# MSP432E401YTPDT_MCU.net
KiCad netlist of a schematic drawn in Altium Designer
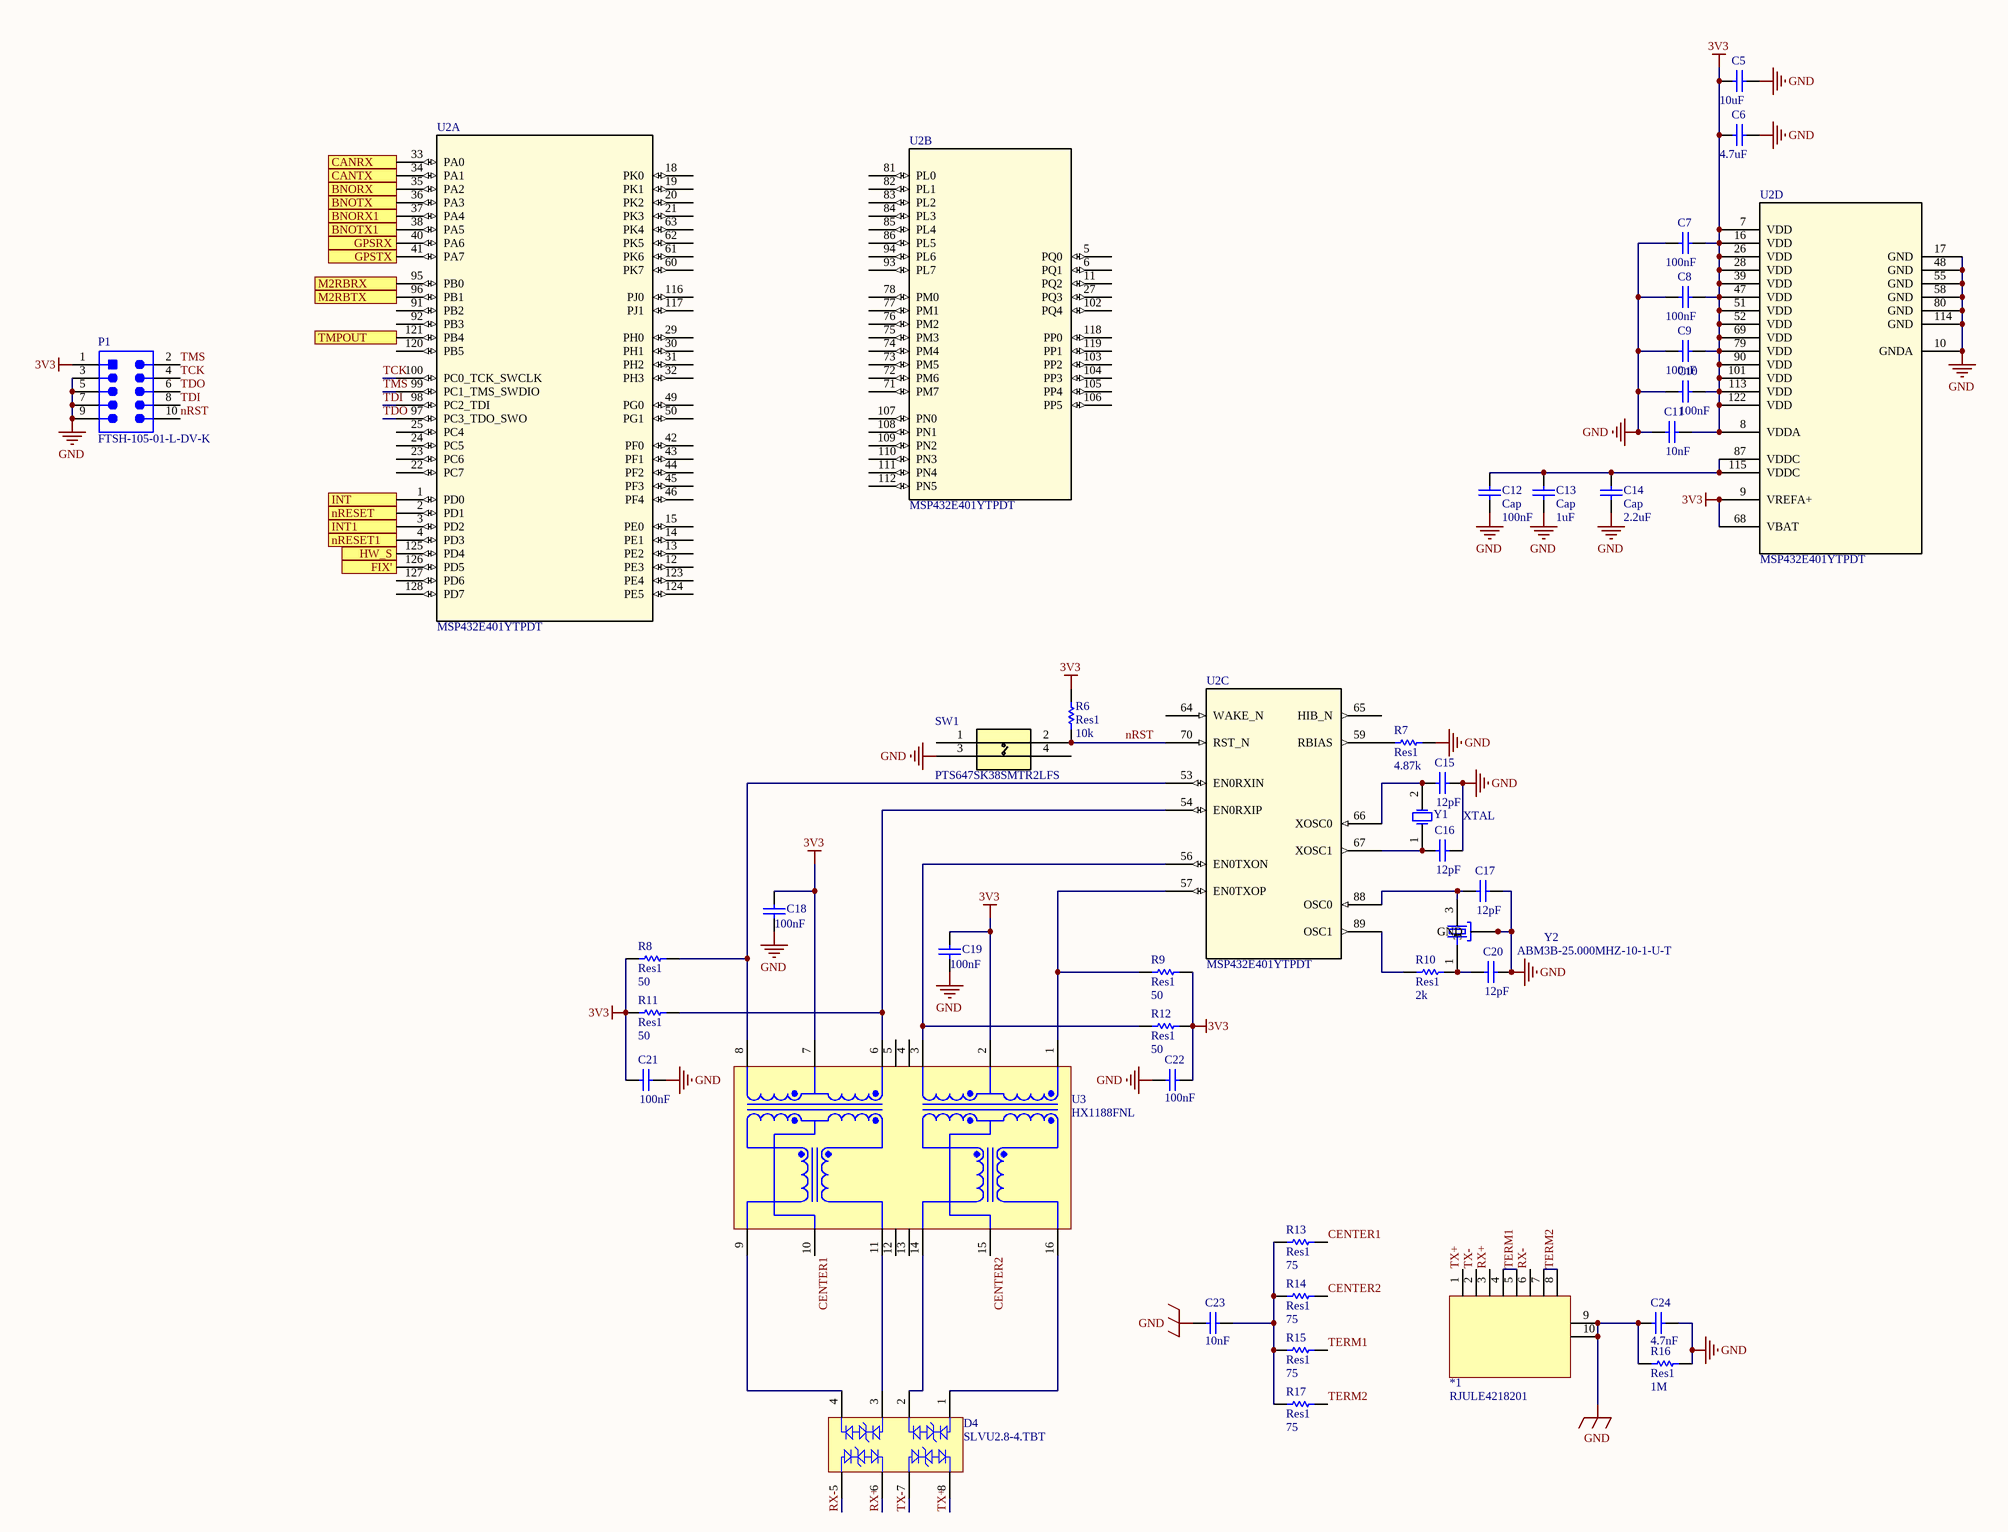
[diagram p0: MSP432E401YTPDT MCU.SchDoc]

(export (version "E")
  (design (tool "Eeschema 10.0.6"))
  (components
    (comp (ref "*1")
      (value "RJULE4218201")
      (footprint "RJULE4218201")
      (libsource (lib "RJULE4218201") (part "RJULE4218201"))
    )
    (comp (ref "C5")
      (value "10uF")
      (footprint "6-0805_M")
      (description "Capacitor")
      (fields (field (name "Comment") "Cap") (field (name "PUBLISHER") "Altium Limited"))
      (libsource (lib "Miscellaneous Devices") (part "Cap"))
    )
    (comp (ref "C6")
      (value "4.7uF")
      (footprint "6-0805_M")
      (description "Capacitor")
      (fields (field (name "Comment") "Cap") (field (name "PUBLISHER") "Altium Limited"))
      (libsource (lib "Miscellaneous Devices") (part "Cap"))
    )
    (comp (ref "C7")
      (value "100nF")
      (footprint "0402-A")
      (description "Capacitor")
      (fields (field (name "Comment") "Cap") (field (name "PUBLISHER") "Altium Limited"))
      (libsource (lib "Miscellaneous Devices") (part "Cap"))
    )
    (comp (ref "C8")
      (value "100nF")
      (footprint "0402-A")
      (description "Capacitor")
      (fields (field (name "Comment") "Cap") (field (name "PUBLISHER") "Altium Limited"))
      (libsource (lib "Miscellaneous Devices") (part "Cap"))
    )
    (comp (ref "C9")
      (value "100nF")
      (footprint "0402-A")
      (description "Capacitor")
      (fields (field (name "Comment") "Cap") (field (name "PUBLISHER") "Altium Limited"))
      (libsource (lib "Miscellaneous Devices") (part "Cap"))
    )
    (comp (ref "C10")
      (value "100nF")
      (footprint "0402-A")
      (description "Capacitor")
      (fields (field (name "Comment") "Cap") (field (name "PUBLISHER") "Altium Limited"))
      (libsource (lib "Miscellaneous Devices") (part "Cap"))
    )
    (comp (ref "C11")
      (value "10nF")
      (footprint "0402-A")
      (description "Capacitor")
      (fields (field (name "Comment") "Cap") (field (name "PUBLISHER") "Altium Limited"))
      (libsource (lib "Miscellaneous Devices") (part "Cap"))
    )
    (comp (ref "C12")
      (value "Cap")
      (footprint "0402-A")
      (description "Capacitor")
      (fields (field (name "ALTIUM_VALUE") "100nF") (field (name "PUBLISHER") "Altium Limited"))
      (libsource (lib "Miscellaneous Devices") (part "Cap"))
    )
    (comp (ref "C13")
      (value "Cap")
      (footprint "1608[0603]")
      (description "Capacitor")
      (fields (field (name "ALTIUM_VALUE") "1uF") (field (name "PUBLISHER") "Altium Limited"))
      (libsource (lib "Miscellaneous Devices") (part "Cap"))
    )
    (comp (ref "C14")
      (value "Cap")
      (footprint "1608[0603]")
      (description "Capacitor")
      (fields (field (name "ALTIUM_VALUE") "2.2uF") (field (name "PUBLISHER") "Altium Limited"))
      (libsource (lib "Miscellaneous Devices") (part "Cap"))
    )
    (comp (ref "C15")
      (value "12pF")
      (footprint "0402-A")
      (description "Capacitor")
      (fields (field (name "Comment") "Cap") (field (name "PUBLISHER") "Altium Limited"))
      (libsource (lib "Miscellaneous Devices") (part "Cap"))
    )
    (comp (ref "C16")
      (value "12pF")
      (footprint "0402-A")
      (description "Capacitor")
      (fields (field (name "Comment") "Cap") (field (name "PUBLISHER") "Altium Limited"))
      (libsource (lib "Miscellaneous Devices") (part "Cap"))
    )
    (comp (ref "C17")
      (value "12pF")
      (footprint "0402-A")
      (description "Capacitor")
      (fields (field (name "Comment") "Cap") (field (name "PUBLISHER") "Altium Limited"))
      (libsource (lib "Miscellaneous Devices") (part "Cap"))
    )
    (comp (ref "C18")
      (value "100nF")
      (footprint "0402-A")
      (description "Capacitor")
      (fields (field (name "Comment") "Cap") (field (name "PUBLISHER") "Altium Limited"))
      (libsource (lib "Miscellaneous Devices") (part "Cap"))
    )
    (comp (ref "C19")
      (value "100nF")
      (footprint "0402-A")
      (description "Capacitor")
      (fields (field (name "Comment") "Cap") (field (name "PUBLISHER") "Altium Limited"))
      (libsource (lib "Miscellaneous Devices") (part "Cap"))
    )
    (comp (ref "C20")
      (value "12pF")
      (footprint "0402-A")
      (description "Capacitor")
      (fields (field (name "Comment") "Cap") (field (name "PUBLISHER") "Altium Limited"))
      (libsource (lib "Miscellaneous Devices") (part "Cap"))
    )
    (comp (ref "C21")
      (value "100nF")
      (footprint "0402-A")
      (description "Capacitor")
      (fields (field (name "Comment") "Cap") (field (name "PUBLISHER") "Altium Limited"))
      (libsource (lib "Miscellaneous Devices") (part "Cap"))
    )
    (comp (ref "C22")
      (value "100nF")
      (footprint "0402-A")
      (description "Capacitor")
      (fields (field (name "Comment") "Cap") (field (name "PUBLISHER") "Altium Limited"))
      (libsource (lib "Miscellaneous Devices") (part "Cap"))
    )
    (comp (ref "C23")
      (value "10nF")
      (footprint "0402-A")
      (description "Capacitor")
      (fields (field (name "Comment") "Cap") (field (name "PUBLISHER") "Altium Limited"))
      (libsource (lib "Miscellaneous Devices") (part "Cap"))
    )
    (comp (ref "C24")
      (value "4.7nF")
      (footprint "C1206")
      (description "Capacitor")
      (fields (field (name "Comment") "Cap") (field (name "PUBLISHER") "Altium Limited"))
      (libsource (lib "Miscellaneous Devices") (part "Cap"))
    )
    (comp (ref "D4")
      (value "SLVU2.8-4.TBT")
      (footprint "SEMT-SO-8_V")
      (fields (field (name "MANUFACTURER") "Semtech"))
      (libsource (lib "Altium Content Vault") (part "SEMT-SLVU2.8-4-SO-8"))
    )
    (comp (ref "P1")
      (value "FTSH-105-01-L-DV-K")
      (footprint "SMTC-FTSH-105-01-L-DV-K_V")
      (description "Male Header, Pitch 1.27 mm, 2 x 5 Position, Height 6.25 mm")
      (fields (field (name "MANUFACTURER") "Samtec"))
      (libsource (lib "Altium Content Vault") (part "CN-2P-M-R10"))
    )
    (comp (ref "R6")
      (value "Res1")
      (footprint "0402-A")
      (description "Resistor")
      (fields (field (name "ALTIUM_VALUE") "10k") (field (name "PUBLISHER") "Altium Limited"))
      (libsource (lib "Miscellaneous Devices") (part "Res1"))
    )
    (comp (ref "R7")
      (value "Res1")
      (footprint "0402-A")
      (description "Resistor")
      (fields (field (name "ALTIUM_VALUE") "4.87k") (field (name "PUBLISHER") "Altium Limited"))
      (libsource (lib "Miscellaneous Devices") (part "Res1"))
    )
    (comp (ref "R8")
      (value "Res1")
      (footprint "0402-A")
      (description "Resistor")
      (fields (field (name "ALTIUM_VALUE") "50") (field (name "PUBLISHER") "Altium Limited"))
      (libsource (lib "Miscellaneous Devices") (part "Res1"))
    )
    (comp (ref "R9")
      (value "Res1")
      (footprint "0402-A")
      (description "Resistor")
      (fields (field (name "ALTIUM_VALUE") "50") (field (name "PUBLISHER") "Altium Limited"))
      (libsource (lib "Miscellaneous Devices") (part "Res1"))
    )
    (comp (ref "R10")
      (value "Res1")
      (footprint "0402-A")
      (description "Resistor")
      (fields (field (name "ALTIUM_VALUE") "2k") (field (name "PUBLISHER") "Altium Limited"))
      (libsource (lib "Miscellaneous Devices") (part "Res1"))
    )
    (comp (ref "R11")
      (value "Res1")
      (footprint "0402-A")
      (description "Resistor")
      (fields (field (name "ALTIUM_VALUE") "50") (field (name "PUBLISHER") "Altium Limited"))
      (libsource (lib "Miscellaneous Devices") (part "Res1"))
    )
    (comp (ref "R12")
      (value "Res1")
      (footprint "0402-A")
      (description "Resistor")
      (fields (field (name "ALTIUM_VALUE") "50") (field (name "PUBLISHER") "Altium Limited"))
      (libsource (lib "Miscellaneous Devices") (part "Res1"))
    )
    (comp (ref "R13")
      (value "Res1")
      (footprint "0402-A")
      (description "Resistor")
      (fields (field (name "ALTIUM_VALUE") "75") (field (name "PUBLISHER") "Altium Limited"))
      (libsource (lib "Miscellaneous Devices") (part "Res1"))
    )
    (comp (ref "R14")
      (value "Res1")
      (footprint "0402-A")
      (description "Resistor")
      (fields (field (name "ALTIUM_VALUE") "75") (field (name "PUBLISHER") "Altium Limited"))
      (libsource (lib "Miscellaneous Devices") (part "Res1"))
    )
    (comp (ref "R15")
      (value "Res1")
      (footprint "0402-A")
      (description "Resistor")
      (fields (field (name "ALTIUM_VALUE") "75") (field (name "PUBLISHER") "Altium Limited"))
      (libsource (lib "Miscellaneous Devices") (part "Res1"))
    )
    (comp (ref "R16")
      (value "Res1")
      (footprint "C1206")
      (description "Resistor")
      (fields (field (name "ALTIUM_VALUE") "1M") (field (name "PUBLISHER") "Altium Limited"))
      (libsource (lib "Miscellaneous Devices") (part "Res1"))
    )
    (comp (ref "R17")
      (value "Res1")
      (footprint "0402-A")
      (description "Resistor")
      (fields (field (name "ALTIUM_VALUE") "75") (field (name "PUBLISHER") "Altium Limited"))
      (libsource (lib "Miscellaneous Devices") (part "Res1"))
    )
    (comp (ref "SW1")
      (value "PTS647SK38SMTR2LFS")
      (footprint "PTS647SK38SMTR2LFS_CNK")
      (description "No Description Available")
      (fields (field (name "COPYRIGHT") "Copyright (C) 2018 Accelerated Designs. All rights reserved"))
      (libsource (lib "PTS 647 SK38 SMTR2 LFS") (part "PTS647SK38SMTR2LFS"))
    )
    (comp (ref "U2")
      (value "MSP432E401YTPDT")
      (footprint "PDT0128A")
      (description "No Description Available")
      (fields
        (field (name "MANUFACTURER") "Texas Instruments")
        (field (name "PARTNUMBER") "MSP432E401YTPDTR")
        (field (name "COPYRIGHT") "Copyright (C) 2018 Accelerated Designs. All rights reserved")
      )
      (libsource (lib "MSP432E401Y") (part "MSP432E401YTPDT"))
    )
    (comp (ref "U3")
      (value "HX1188FNL")
      (footprint "PULS-HX1188FNL-SMT-16_V")
      (description "Telecom Transformer 1:1/1:1, -40 to 85 degC, 16-Pin SMT, RoHS, Tube")
      (fields (field (name "MANUFACTURER") "Pulse Electronics"))
      (libsource (lib "Altium Content Vault") (part "PULS-HX1188FNL-16"))
    )
    (comp (ref "Y1")
      (value "XTAL")
      (footprint "FC-135 32.7680KA-AC0")
      (description "Crystal Oscillator")
      (fields (field (name "PUBLISHER") "Altium Limited"))
      (libsource (lib "Miscellaneous Devices") (part "XTAL"))
    )
    (comp (ref "Y2")
      (value "ABM3B-25.000MHZ-10-1-U-T")
      (footprint "OSCCC500X320X110-4N")
      (description "25MHz Â±10ppm Crystal 10pF 50 Ohms 4-SMD, No Lead")
      (fields (field (name "MF") "Abracon"))
      (libsource (lib "ABM3B-25.000MHZ-10-1-U-T") (part "ABM3B-25.000MHZ-10-1-U-T"))
    )
  )
  (nets
    (net (code "1") (name "/BNORX") (class "Default")
      (node (ref "U2") (pin "35") (pinfunction "PA2_35") (pintype "bidirectional"))
    )
    (net (code "2") (name "/BNORX1") (class "Default")
      (node (ref "U2") (pin "37") (pinfunction "PA4_37") (pintype "bidirectional"))
    )
    (net (code "3") (name "/BNOTX") (class "Default")
      (node (ref "U2") (pin "36") (pinfunction "PA3_36") (pintype "bidirectional"))
    )
    (net (code "4") (name "/BNOTX1") (class "Default")
      (node (ref "U2") (pin "38") (pinfunction "PA5_38") (pintype "bidirectional"))
    )
    (net (code "5") (name "/CANRX") (class "Default")
      (node (ref "U2") (pin "33") (pinfunction "PA0_33") (pintype "bidirectional"))
    )
    (net (code "6") (name "/CANTX") (class "Default")
      (node (ref "U2") (pin "34") (pinfunction "PA1_34") (pintype "bidirectional"))
    )
    (net (code "7") (name "/CENTER1") (class "Default")
      (node (ref "R13") (pin "2") (pinfunction "2_2") (pintype "passive"))
      (node (ref "U3") (pin "10") (pinfunction "CMT_10") (pintype "passive"))
    )
    (net (code "8") (name "/CENTER2") (class "Default")
      (node (ref "R14") (pin "2") (pinfunction "2_2") (pintype "passive"))
      (node (ref "U3") (pin "15") (pinfunction "CMT_15") (pintype "passive"))
    )
    (net (code "9") (name "/FIX'") (class "Default")
      (node (ref "U2") (pin "126") (pinfunction "PD5_126") (pintype "bidirectional"))
    )
    (net (code "10") (name "/GPSRX") (class "Default")
      (node (ref "U2") (pin "40") (pinfunction "PA6_40") (pintype "bidirectional"))
    )
    (net (code "11") (name "/GPSTX") (class "Default")
      (node (ref "U2") (pin "41") (pinfunction "PA7_41") (pintype "bidirectional"))
    )
    (net (code "12") (name "/HW_S") (class "Default")
      (node (ref "U2") (pin "125") (pinfunction "PD4_125") (pintype "bidirectional"))
    )
    (net (code "13") (name "/INT") (class "Default")
      (node (ref "U2") (pin "1") (pinfunction "PD0_1") (pintype "bidirectional"))
    )
    (net (code "14") (name "/INT1") (class "Default")
      (node (ref "U2") (pin "3") (pinfunction "PD2_3") (pintype "bidirectional"))
    )
    (net (code "15") (name "/M2RBRX") (class "Default")
      (node (ref "U2") (pin "95") (pinfunction "PB0_95") (pintype "bidirectional"))
    )
    (net (code "16") (name "/M2RBTX") (class "Default")
      (node (ref "U2") (pin "96") (pinfunction "PB1_96") (pintype "bidirectional"))
    )
    (net (code "17") (name "/RX+") (class "Default")
      (node (ref "*1") (pin "3") (pinfunction "13_3") (pintype "passive"))
      (node (ref "D4") (pin "6") (pinfunction "6_6") (pintype "passive"))
    )
    (net (code "18") (name "/RX-") (class "Default")
      (node (ref "*1") (pin "6") (pinfunction "16_6") (pintype "passive"))
      (node (ref "D4") (pin "5") (pinfunction "5_5") (pintype "passive"))
    )
    (net (code "19") (name "/TCK") (class "Default")
      (node (ref "P1") (pin "4") (pinfunction "4_4") (pintype "passive"))
      (node (ref "U2") (pin "100") (pinfunction "PC0_TCK_SWCLK_100") (pintype "bidirectional"))
    )
    (net (code "20") (name "/TDI") (class "Default")
      (node (ref "P1") (pin "8") (pinfunction "8_8") (pintype "passive"))
      (node (ref "U2") (pin "98") (pinfunction "PC2_TDI_98") (pintype "bidirectional"))
    )
    (net (code "21") (name "/TDO") (class "Default")
      (node (ref "P1") (pin "6") (pinfunction "6_6") (pintype "passive"))
      (node (ref "U2") (pin "97") (pinfunction "PC3_TDO_SWO_97") (pintype "bidirectional"))
    )
    (net (code "22") (name "/TERM1") (class "Default")
      (node (ref "*1") (pin "4") (pinfunction "14_4") (pintype "passive"))
      (node (ref "*1") (pin "5") (pinfunction "15_5") (pintype "passive"))
      (node (ref "R15") (pin "2") (pinfunction "2_2") (pintype "passive"))
    )
    (net (code "23") (name "/TERM2") (class "Default")
      (node (ref "*1") (pin "7") (pinfunction "17_7") (pintype "passive"))
      (node (ref "*1") (pin "8") (pinfunction "18_8") (pintype "passive"))
      (node (ref "R17") (pin "2") (pinfunction "2_2") (pintype "passive"))
    )
    (net (code "24") (name "/TMPOUT") (class "Default")
      (node (ref "U2") (pin "121") (pinfunction "PB4_121") (pintype "bidirectional"))
    )
    (net (code "25") (name "/TMS") (class "Default")
      (node (ref "P1") (pin "2") (pinfunction "2_2") (pintype "passive"))
      (node (ref "U2") (pin "99") (pinfunction "PC1_TMS_SWDIO_99") (pintype "bidirectional"))
    )
    (net (code "26") (name "/TX+") (class "Default")
      (node (ref "*1") (pin "1") (pinfunction "11_1") (pintype "passive"))
      (node (ref "D4") (pin "8") (pinfunction "8_8") (pintype "passive"))
    )
    (net (code "27") (name "/TX-") (class "Default")
      (node (ref "*1") (pin "2") (pinfunction "12_2") (pintype "passive"))
      (node (ref "D4") (pin "7") (pinfunction "7_7") (pintype "passive"))
    )
    (net (code "28") (name "/nRESET") (class "Default")
      (node (ref "U2") (pin "2") (pinfunction "PD1_2") (pintype "bidirectional"))
    )
    (net (code "29") (name "/nRESET1") (class "Default")
      (node (ref "U2") (pin "4") (pinfunction "PD3_4") (pintype "bidirectional"))
    )
    (net (code "30") (name "/nRST") (class "Default")
      (node (ref "P1") (pin "10") (pinfunction "10_10") (pintype "passive"))
      (node (ref "R6") (pin "2") (pinfunction "2_2") (pintype "passive"))
      (node (ref "SW1") (pin "2") (pinfunction "2_2") (pintype "passive"))
      (node (ref "U2") (pin "70") (pinfunction "RST_N_70") (pintype "input"))
    )
    (net (code "31") (name "3V3") (class "Default")
      (node (ref "C10") (pin "2") (pinfunction "2_2") (pintype "passive"))
      (node (ref "C11") (pin "2") (pinfunction "2_2") (pintype "passive"))
      (node (ref "C18") (pin "1") (pinfunction "1_1") (pintype "passive"))
      (node (ref "C19") (pin "1") (pinfunction "1_1") (pintype "passive"))
      (node (ref "C21") (pin "1") (pinfunction "1_1") (pintype "passive"))
      (node (ref "C22") (pin "1") (pinfunction "1_1") (pintype "passive"))
      (node (ref "C5") (pin "1") (pinfunction "1_1") (pintype "passive"))
      (node (ref "C6") (pin "1") (pinfunction "1_1") (pintype "passive"))
      (node (ref "C7") (pin "2") (pinfunction "2_2") (pintype "passive"))
      (node (ref "C8") (pin "2") (pinfunction "2_2") (pintype "passive"))
      (node (ref "C9") (pin "2") (pinfunction "2_2") (pintype "passive"))
      (node (ref "P1") (pin "1") (pinfunction "1_1") (pintype "passive"))
      (node (ref "R11") (pin "1") (pinfunction "1_1") (pintype "passive"))
      (node (ref "R12") (pin "1") (pinfunction "1_1") (pintype "passive"))
      (node (ref "R6") (pin "1") (pinfunction "1_1") (pintype "passive"))
      (node (ref "R8") (pin "1") (pinfunction "1_1") (pintype "passive"))
      (node (ref "R9") (pin "1") (pinfunction "1_1") (pintype "passive"))
      (node (ref "U2") (pin "101") (pinfunction "VDD_101") (pintype "power_in"))
      (node (ref "U2") (pin "113") (pinfunction "VDD_113") (pintype "power_in"))
      (node (ref "U2") (pin "122") (pinfunction "VDD_122") (pintype "power_in"))
      (node (ref "U2") (pin "16") (pinfunction "VDD_16") (pintype "power_in"))
      (node (ref "U2") (pin "26") (pinfunction "VDD_26") (pintype "power_in"))
      (node (ref "U2") (pin "28") (pinfunction "VDD_28") (pintype "power_in"))
      (node (ref "U2") (pin "39") (pinfunction "VDD_39") (pintype "power_in"))
      (node (ref "U2") (pin "47") (pinfunction "VDD_47") (pintype "power_in"))
      (node (ref "U2") (pin "51") (pinfunction "VDD_51") (pintype "power_in"))
      (node (ref "U2") (pin "52") (pinfunction "VDD_52") (pintype "power_in"))
      (node (ref "U2") (pin "68") (pinfunction "VBAT_68") (pintype "power_in"))
      (node (ref "U2") (pin "69") (pinfunction "VDD_69") (pintype "power_in"))
      (node (ref "U2") (pin "7") (pinfunction "VDD_7") (pintype "power_in"))
      (node (ref "U2") (pin "79") (pinfunction "VDD_79") (pintype "power_in"))
      (node (ref "U2") (pin "8") (pinfunction "VDDA_8") (pintype "power_in"))
      (node (ref "U2") (pin "9") (pinfunction "VREFA+_9") (pintype "power_in"))
      (node (ref "U2") (pin "90") (pinfunction "VDD_90") (pintype "power_in"))
      (node (ref "U3") (pin "2") (pinfunction "TCT_2") (pintype "passive"))
      (node (ref "U3") (pin "7") (pinfunction "RCT_7") (pintype "passive"))
    )
    (net (code "32") (name "GND") (class "Default")
      (node (ref "*1") (pin "10") (pinfunction "10_10") (pintype "passive"))
      (node (ref "*1") (pin "9") (pinfunction "9_9") (pintype "passive"))
      (node (ref "C10") (pin "1") (pinfunction "1_1") (pintype "passive"))
      (node (ref "C11") (pin "1") (pinfunction "1_1") (pintype "passive"))
      (node (ref "C12") (pin "1") (pinfunction "1_1") (pintype "passive"))
      (node (ref "C13") (pin "1") (pinfunction "1_1") (pintype "passive"))
      (node (ref "C14") (pin "1") (pinfunction "1_1") (pintype "passive"))
      (node (ref "C15") (pin "1") (pinfunction "1_1") (pintype "passive"))
      (node (ref "C16") (pin "1") (pinfunction "1_1") (pintype "passive"))
      (node (ref "C17") (pin "1") (pinfunction "1_1") (pintype "passive"))
      (node (ref "C18") (pin "2") (pinfunction "2_2") (pintype "passive"))
      (node (ref "C19") (pin "2") (pinfunction "2_2") (pintype "passive"))
      (node (ref "C20") (pin "1") (pinfunction "1_1") (pintype "passive"))
      (node (ref "C21") (pin "2") (pinfunction "2_2") (pintype "passive"))
      (node (ref "C22") (pin "2") (pinfunction "2_2") (pintype "passive"))
      (node (ref "C23") (pin "1") (pinfunction "1_1") (pintype "passive"))
      (node (ref "C24") (pin "1") (pinfunction "1_1") (pintype "passive"))
      (node (ref "C24") (pin "2") (pinfunction "2_2") (pintype "passive"))
      (node (ref "C5") (pin "2") (pinfunction "2_2") (pintype "passive"))
      (node (ref "C6") (pin "2") (pinfunction "2_2") (pintype "passive"))
      (node (ref "C7") (pin "1") (pinfunction "1_1") (pintype "passive"))
      (node (ref "C8") (pin "1") (pinfunction "1_1") (pintype "passive"))
      (node (ref "C9") (pin "1") (pinfunction "1_1") (pintype "passive"))
      (node (ref "P1") (pin "3") (pinfunction "3_3") (pintype "passive"))
      (node (ref "P1") (pin "5") (pinfunction "5_5") (pintype "passive"))
      (node (ref "P1") (pin "7") (pinfunction "7_7") (pintype "passive"))
      (node (ref "P1") (pin "9") (pinfunction "9_9") (pintype "passive"))
      (node (ref "R16") (pin "1") (pinfunction "1_1") (pintype "passive"))
      (node (ref "R16") (pin "2") (pinfunction "2_2") (pintype "passive"))
      (node (ref "R7") (pin "1") (pinfunction "1_1") (pintype "passive"))
      (node (ref "SW1") (pin "3") (pinfunction "3_3") (pintype "passive"))
      (node (ref "U2") (pin "10") (pinfunction "GNDA_10") (pintype "power_in"))
      (node (ref "U2") (pin "114") (pinfunction "GND_114") (pintype "power_in"))
      (node (ref "U2") (pin "17") (pinfunction "GND_17") (pintype "power_in"))
      (node (ref "U2") (pin "48") (pinfunction "GND_48") (pintype "power_in"))
      (node (ref "U2") (pin "55") (pinfunction "GND_55") (pintype "power_in"))
      (node (ref "U2") (pin "58") (pinfunction "GND_58") (pintype "power_in"))
      (node (ref "U2") (pin "80") (pinfunction "GND_80") (pintype "power_in"))
      (node (ref "Y2") (pin "2") (pinfunction "GND_2") (pintype "passive"))
      (node (ref "Y2") (pin "4") (pinfunction "GND_4") (pintype "passive"))
    )
    (net (code "33") (name "Net-(C12-Pad2)") (class "Default")
      (node (ref "C12") (pin "2") (pinfunction "2_2") (pintype "passive"))
      (node (ref "C13") (pin "2") (pinfunction "2_2") (pintype "passive"))
      (node (ref "C14") (pin "2") (pinfunction "2_2") (pintype "passive"))
      (node (ref "U2") (pin "115") (pinfunction "VDDC_115") (pintype "power_in"))
      (node (ref "U2") (pin "87") (pinfunction "VDDC_87") (pintype "power_in"))
    )
    (net (code "34") (name "Net-(C20-Pad2)") (class "Default")
      (node (ref "C20") (pin "2") (pinfunction "2_2") (pintype "passive"))
      (node (ref "R10") (pin "2") (pinfunction "2_2") (pintype "passive"))
      (node (ref "Y2") (pin "1") (pinfunction "1_1") (pintype "passive"))
    )
    (net (code "35") (name "Net-(C23-Pad2)") (class "Default")
      (node (ref "C23") (pin "2") (pinfunction "2_2") (pintype "passive"))
      (node (ref "R13") (pin "1") (pinfunction "1_1") (pintype "passive"))
      (node (ref "R14") (pin "1") (pinfunction "1_1") (pintype "passive"))
      (node (ref "R15") (pin "1") (pinfunction "1_1") (pintype "passive"))
      (node (ref "R17") (pin "1") (pinfunction "1_1") (pintype "passive"))
    )
    (net (code "36") (name "Net-(U2C-EN0RXIN)") (class "Default")
      (node (ref "R8") (pin "2") (pinfunction "2_2") (pintype "passive"))
      (node (ref "U2") (pin "53") (pinfunction "EN0RXIN_53") (pintype "bidirectional"))
      (node (ref "U3") (pin "8") (pinfunction "RD-_8") (pintype "passive"))
    )
    (net (code "37") (name "Net-(U2C-EN0RXIP)") (class "Default")
      (node (ref "R11") (pin "2") (pinfunction "2_2") (pintype "passive"))
      (node (ref "U2") (pin "54") (pinfunction "EN0RXIP_54") (pintype "bidirectional"))
      (node (ref "U3") (pin "6") (pinfunction "RD+_6") (pintype "passive"))
    )
    (net (code "38") (name "Net-(U2C-EN0TXON)") (class "Default")
      (node (ref "R12") (pin "2") (pinfunction "2_2") (pintype "passive"))
      (node (ref "U2") (pin "56") (pinfunction "EN0TXON_56") (pintype "bidirectional"))
      (node (ref "U3") (pin "3") (pinfunction "TD-_3") (pintype "passive"))
    )
    (net (code "39") (name "Net-(U2C-EN0TXOP)") (class "Default")
      (node (ref "R9") (pin "2") (pinfunction "2_2") (pintype "passive"))
      (node (ref "U2") (pin "57") (pinfunction "EN0TXOP_57") (pintype "bidirectional"))
      (node (ref "U3") (pin "1") (pinfunction "TD+_1") (pintype "passive"))
    )
    (net (code "40") (name "Net-(U2C-OSC0)") (class "Default")
      (node (ref "C17") (pin "2") (pinfunction "2_2") (pintype "passive"))
      (node (ref "U2") (pin "88") (pinfunction "OSC0_88") (pintype "input"))
      (node (ref "Y2") (pin "3") (pinfunction "3_3") (pintype "passive"))
    )
    (net (code "41") (name "Net-(U2C-OSC1)") (class "Default")
      (node (ref "R10") (pin "1") (pinfunction "1_1") (pintype "passive"))
      (node (ref "U2") (pin "89") (pinfunction "OSC1_89") (pintype "output"))
    )
    (net (code "42") (name "Net-(U2C-RBIAS)") (class "Default")
      (node (ref "R7") (pin "2") (pinfunction "2_2") (pintype "passive"))
      (node (ref "U2") (pin "59") (pinfunction "RBIAS_59") (pintype "output"))
    )
    (net (code "43") (name "Net-(U2C-XOSC0)") (class "Default")
      (node (ref "C15") (pin "2") (pinfunction "2_2") (pintype "passive"))
      (node (ref "U2") (pin "66") (pinfunction "XOSC0_66") (pintype "input"))
      (node (ref "Y1") (pin "2") (pinfunction "OSC2_2") (pintype "passive"))
    )
    (net (code "44") (name "Net-(U2C-XOSC1)") (class "Default")
      (node (ref "C16") (pin "2") (pinfunction "2_2") (pintype "passive"))
      (node (ref "U2") (pin "67") (pinfunction "XOSC1_67") (pintype "output"))
      (node (ref "Y1") (pin "1") (pinfunction "OSC1_1") (pintype "passive"))
    )
    (net (code "45") (name "Net-(U3-RX+)") (class "Default")
      (node (ref "D4") (pin "3") (pinfunction "3_3") (pintype "passive"))
      (node (ref "U3") (pin "11") (pinfunction "RX+_11") (pintype "passive"))
    )
    (net (code "46") (name "Net-(U3-RX-)") (class "Default")
      (node (ref "D4") (pin "4") (pinfunction "4_4") (pintype "passive"))
      (node (ref "U3") (pin "9") (pinfunction "RX-_9") (pintype "passive"))
    )
    (net (code "47") (name "Net-(U3-TX+)") (class "Default")
      (node (ref "D4") (pin "1") (pinfunction "1_1") (pintype "passive"))
      (node (ref "U3") (pin "16") (pinfunction "TX+_16") (pintype "passive"))
    )
    (net (code "48") (name "Net-(U3-TX-)") (class "Default")
      (node (ref "D4") (pin "2") (pinfunction "2_2") (pintype "passive"))
      (node (ref "U3") (pin "14") (pinfunction "TX-_14") (pintype "passive"))
    )
    (net (code "49") (name "unconnected-(SW1-Pad1)") (class "Default")
      (node (ref "SW1") (pin "1") (pinfunction "1_1") (pintype "passive"))
    )
    (net (code "50") (name "unconnected-(SW1-Pad4)") (class "Default")
      (node (ref "SW1") (pin "4") (pinfunction "4_4") (pintype "passive"))
    )
    (net (code "51") (name "unconnected-(U2A-PB2-Pad91)") (class "Default")
      (node (ref "U2") (pin "91") (pinfunction "PB2_91") (pintype "bidirectional"))
    )
    (net (code "52") (name "unconnected-(U2A-PB3-Pad92)") (class "Default")
      (node (ref "U2") (pin "92") (pinfunction "PB3_92") (pintype "bidirectional"))
    )
    (net (code "53") (name "unconnected-(U2A-PB5-Pad120)") (class "Default")
      (node (ref "U2") (pin "120") (pinfunction "PB5_120") (pintype "bidirectional"))
    )
    (net (code "54") (name "unconnected-(U2A-PC4-Pad25)") (class "Default")
      (node (ref "U2") (pin "25") (pinfunction "PC4_25") (pintype "bidirectional"))
    )
    (net (code "55") (name "unconnected-(U2A-PC5-Pad24)") (class "Default")
      (node (ref "U2") (pin "24") (pinfunction "PC5_24") (pintype "bidirectional"))
    )
    (net (code "56") (name "unconnected-(U2A-PC6-Pad23)") (class "Default")
      (node (ref "U2") (pin "23") (pinfunction "PC6_23") (pintype "bidirectional"))
    )
    (net (code "57") (name "unconnected-(U2A-PC7-Pad22)") (class "Default")
      (node (ref "U2") (pin "22") (pinfunction "PC7_22") (pintype "bidirectional"))
    )
    (net (code "58") (name "unconnected-(U2A-PD6-Pad127)") (class "Default")
      (node (ref "U2") (pin "127") (pinfunction "PD6_127") (pintype "bidirectional"))
    )
    (net (code "59") (name "unconnected-(U2A-PD7-Pad128)") (class "Default")
      (node (ref "U2") (pin "128") (pinfunction "PD7_128") (pintype "bidirectional"))
    )
    (net (code "60") (name "unconnected-(U2A-PE0-Pad15)") (class "Default")
      (node (ref "U2") (pin "15") (pinfunction "PE0_15") (pintype "bidirectional"))
    )
    (net (code "61") (name "unconnected-(U2A-PE1-Pad14)") (class "Default")
      (node (ref "U2") (pin "14") (pinfunction "PE1_14") (pintype "bidirectional"))
    )
    (net (code "62") (name "unconnected-(U2A-PE2-Pad13)") (class "Default")
      (node (ref "U2") (pin "13") (pinfunction "PE2_13") (pintype "bidirectional"))
    )
    (net (code "63") (name "unconnected-(U2A-PE3-Pad12)") (class "Default")
      (node (ref "U2") (pin "12") (pinfunction "PE3_12") (pintype "bidirectional"))
    )
    (net (code "64") (name "unconnected-(U2A-PE4-Pad123)") (class "Default")
      (node (ref "U2") (pin "123") (pinfunction "PE4_123") (pintype "bidirectional"))
    )
    (net (code "65") (name "unconnected-(U2A-PE5-Pad124)") (class "Default")
      (node (ref "U2") (pin "124") (pinfunction "PE5_124") (pintype "bidirectional"))
    )
    (net (code "66") (name "unconnected-(U2A-PF0-Pad42)") (class "Default")
      (node (ref "U2") (pin "42") (pinfunction "PF0_42") (pintype "bidirectional"))
    )
    (net (code "67") (name "unconnected-(U2A-PF1-Pad43)") (class "Default")
      (node (ref "U2") (pin "43") (pinfunction "PF1_43") (pintype "bidirectional"))
    )
    (net (code "68") (name "unconnected-(U2A-PF2-Pad44)") (class "Default")
      (node (ref "U2") (pin "44") (pinfunction "PF2_44") (pintype "bidirectional"))
    )
    (net (code "69") (name "unconnected-(U2A-PF3-Pad45)") (class "Default")
      (node (ref "U2") (pin "45") (pinfunction "PF3_45") (pintype "bidirectional"))
    )
    (net (code "70") (name "unconnected-(U2A-PF4-Pad46)") (class "Default")
      (node (ref "U2") (pin "46") (pinfunction "PF4_46") (pintype "bidirectional"))
    )
    (net (code "71") (name "unconnected-(U2A-PG0-Pad49)") (class "Default")
      (node (ref "U2") (pin "49") (pinfunction "PG0_49") (pintype "bidirectional"))
    )
    (net (code "72") (name "unconnected-(U2A-PG1-Pad50)") (class "Default")
      (node (ref "U2") (pin "50") (pinfunction "PG1_50") (pintype "bidirectional"))
    )
    (net (code "73") (name "unconnected-(U2A-PH0-Pad29)") (class "Default")
      (node (ref "U2") (pin "29") (pinfunction "PH0_29") (pintype "bidirectional"))
    )
    (net (code "74") (name "unconnected-(U2A-PH1-Pad30)") (class "Default")
      (node (ref "U2") (pin "30") (pinfunction "PH1_30") (pintype "bidirectional"))
    )
    (net (code "75") (name "unconnected-(U2A-PH2-Pad31)") (class "Default")
      (node (ref "U2") (pin "31") (pinfunction "PH2_31") (pintype "bidirectional"))
    )
    (net (code "76") (name "unconnected-(U2A-PH3-Pad32)") (class "Default")
      (node (ref "U2") (pin "32") (pinfunction "PH3_32") (pintype "bidirectional"))
    )
    (net (code "77") (name "unconnected-(U2A-PJ0-Pad116)") (class "Default")
      (node (ref "U2") (pin "116") (pinfunction "PJ0_116") (pintype "bidirectional"))
    )
    (net (code "78") (name "unconnected-(U2A-PJ1-Pad117)") (class "Default")
      (node (ref "U2") (pin "117") (pinfunction "PJ1_117") (pintype "bidirectional"))
    )
    (net (code "79") (name "unconnected-(U2A-PK0-Pad18)") (class "Default")
      (node (ref "U2") (pin "18") (pinfunction "PK0_18") (pintype "bidirectional"))
    )
    (net (code "80") (name "unconnected-(U2A-PK1-Pad19)") (class "Default")
      (node (ref "U2") (pin "19") (pinfunction "PK1_19") (pintype "bidirectional"))
    )
    (net (code "81") (name "unconnected-(U2A-PK2-Pad20)") (class "Default")
      (node (ref "U2") (pin "20") (pinfunction "PK2_20") (pintype "bidirectional"))
    )
    (net (code "82") (name "unconnected-(U2A-PK3-Pad21)") (class "Default")
      (node (ref "U2") (pin "21") (pinfunction "PK3_21") (pintype "bidirectional"))
    )
    (net (code "83") (name "unconnected-(U2A-PK4-Pad63)") (class "Default")
      (node (ref "U2") (pin "63") (pinfunction "PK4_63") (pintype "bidirectional"))
    )
    (net (code "84") (name "unconnected-(U2A-PK5-Pad62)") (class "Default")
      (node (ref "U2") (pin "62") (pinfunction "PK5_62") (pintype "bidirectional"))
    )
    (net (code "85") (name "unconnected-(U2A-PK6-Pad61)") (class "Default")
      (node (ref "U2") (pin "61") (pinfunction "PK6_61") (pintype "bidirectional"))
    )
    (net (code "86") (name "unconnected-(U2A-PK7-Pad60)") (class "Default")
      (node (ref "U2") (pin "60") (pinfunction "PK7_60") (pintype "bidirectional"))
    )
    (net (code "87") (name "unconnected-(U2B-PL0-Pad81)") (class "Default")
      (node (ref "U2") (pin "81") (pinfunction "PL0_81") (pintype "bidirectional"))
    )
    (net (code "88") (name "unconnected-(U2B-PL1-Pad82)") (class "Default")
      (node (ref "U2") (pin "82") (pinfunction "PL1_82") (pintype "bidirectional"))
    )
    (net (code "89") (name "unconnected-(U2B-PL2-Pad83)") (class "Default")
      (node (ref "U2") (pin "83") (pinfunction "PL2_83") (pintype "bidirectional"))
    )
    (net (code "90") (name "unconnected-(U2B-PL3-Pad84)") (class "Default")
      (node (ref "U2") (pin "84") (pinfunction "PL3_84") (pintype "bidirectional"))
    )
    (net (code "91") (name "unconnected-(U2B-PL4-Pad85)") (class "Default")
      (node (ref "U2") (pin "85") (pinfunction "PL4_85") (pintype "bidirectional"))
    )
    (net (code "92") (name "unconnected-(U2B-PL5-Pad86)") (class "Default")
      (node (ref "U2") (pin "86") (pinfunction "PL5_86") (pintype "bidirectional"))
    )
    (net (code "93") (name "unconnected-(U2B-PL6-Pad94)") (class "Default")
      (node (ref "U2") (pin "94") (pinfunction "PL6_94") (pintype "bidirectional"))
    )
    (net (code "94") (name "unconnected-(U2B-PL7-Pad93)") (class "Default")
      (node (ref "U2") (pin "93") (pinfunction "PL7_93") (pintype "bidirectional"))
    )
    (net (code "95") (name "unconnected-(U2B-PM0-Pad78)") (class "Default")
      (node (ref "U2") (pin "78") (pinfunction "PM0_78") (pintype "bidirectional"))
    )
    (net (code "96") (name "unconnected-(U2B-PM1-Pad77)") (class "Default")
      (node (ref "U2") (pin "77") (pinfunction "PM1_77") (pintype "bidirectional"))
    )
    (net (code "97") (name "unconnected-(U2B-PM2-Pad76)") (class "Default")
      (node (ref "U2") (pin "76") (pinfunction "PM2_76") (pintype "bidirectional"))
    )
    (net (code "98") (name "unconnected-(U2B-PM3-Pad75)") (class "Default")
      (node (ref "U2") (pin "75") (pinfunction "PM3_75") (pintype "bidirectional"))
    )
    (net (code "99") (name "unconnected-(U2B-PM4-Pad74)") (class "Default")
      (node (ref "U2") (pin "74") (pinfunction "PM4_74") (pintype "bidirectional"))
    )
    (net (code "100") (name "unconnected-(U2B-PM5-Pad73)") (class "Default")
      (node (ref "U2") (pin "73") (pinfunction "PM5_73") (pintype "bidirectional"))
    )
    (net (code "101") (name "unconnected-(U2B-PM6-Pad72)") (class "Default")
      (node (ref "U2") (pin "72") (pinfunction "PM6_72") (pintype "bidirectional"))
    )
    (net (code "102") (name "unconnected-(U2B-PM7-Pad71)") (class "Default")
      (node (ref "U2") (pin "71") (pinfunction "PM7_71") (pintype "bidirectional"))
    )
    (net (code "103") (name "unconnected-(U2B-PN0-Pad107)") (class "Default")
      (node (ref "U2") (pin "107") (pinfunction "PN0_107") (pintype "bidirectional"))
    )
    (net (code "104") (name "unconnected-(U2B-PN1-Pad108)") (class "Default")
      (node (ref "U2") (pin "108") (pinfunction "PN1_108") (pintype "bidirectional"))
    )
    (net (code "105") (name "unconnected-(U2B-PN2-Pad109)") (class "Default")
      (node (ref "U2") (pin "109") (pinfunction "PN2_109") (pintype "bidirectional"))
    )
    (net (code "106") (name "unconnected-(U2B-PN3-Pad110)") (class "Default")
      (node (ref "U2") (pin "110") (pinfunction "PN3_110") (pintype "bidirectional"))
    )
    (net (code "107") (name "unconnected-(U2B-PN4-Pad111)") (class "Default")
      (node (ref "U2") (pin "111") (pinfunction "PN4_111") (pintype "bidirectional"))
    )
    (net (code "108") (name "unconnected-(U2B-PN5-Pad112)") (class "Default")
      (node (ref "U2") (pin "112") (pinfunction "PN5_112") (pintype "bidirectional"))
    )
    (net (code "109") (name "unconnected-(U2B-PP0-Pad118)") (class "Default")
      (node (ref "U2") (pin "118") (pinfunction "PP0_118") (pintype "bidirectional"))
    )
    (net (code "110") (name "unconnected-(U2B-PP1-Pad119)") (class "Default")
      (node (ref "U2") (pin "119") (pinfunction "PP1_119") (pintype "bidirectional"))
    )
    (net (code "111") (name "unconnected-(U2B-PP2-Pad103)") (class "Default")
      (node (ref "U2") (pin "103") (pinfunction "PP2_103") (pintype "bidirectional"))
    )
    (net (code "112") (name "unconnected-(U2B-PP3-Pad104)") (class "Default")
      (node (ref "U2") (pin "104") (pinfunction "PP3_104") (pintype "bidirectional"))
    )
    (net (code "113") (name "unconnected-(U2B-PP4-Pad105)") (class "Default")
      (node (ref "U2") (pin "105") (pinfunction "PP4_105") (pintype "bidirectional"))
    )
    (net (code "114") (name "unconnected-(U2B-PP5-Pad106)") (class "Default")
      (node (ref "U2") (pin "106") (pinfunction "PP5_106") (pintype "bidirectional"))
    )
    (net (code "115") (name "unconnected-(U2B-PQ0-Pad5)") (class "Default")
      (node (ref "U2") (pin "5") (pinfunction "PQ0_5") (pintype "bidirectional"))
    )
    (net (code "116") (name "unconnected-(U2B-PQ1-Pad6)") (class "Default")
      (node (ref "U2") (pin "6") (pinfunction "PQ1_6") (pintype "bidirectional"))
    )
    (net (code "117") (name "unconnected-(U2B-PQ2-Pad11)") (class "Default")
      (node (ref "U2") (pin "11") (pinfunction "PQ2_11") (pintype "bidirectional"))
    )
    (net (code "118") (name "unconnected-(U2B-PQ3-Pad27)") (class "Default")
      (node (ref "U2") (pin "27") (pinfunction "PQ3_27") (pintype "bidirectional"))
    )
    (net (code "119") (name "unconnected-(U2B-PQ4-Pad102)") (class "Default")
      (node (ref "U2") (pin "102") (pinfunction "PQ4_102") (pintype "bidirectional"))
    )
    (net (code "120") (name "unconnected-(U2C-HIB_N-Pad65)") (class "Default")
      (node (ref "U2") (pin "65") (pinfunction "HIB_N_65") (pintype "output"))
    )
    (net (code "121") (name "unconnected-(U2C-WAKE_N-Pad64)") (class "Default")
      (node (ref "U2") (pin "64") (pinfunction "WAKE_N_64") (pintype "input"))
    )
    (net (code "122") (name "unconnected-(U3-NC-Pad4)") (class "Default")
      (node (ref "U3") (pin "4") (pinfunction "NC_4") (pintype "passive"))
    )
    (net (code "123") (name "unconnected-(U3-NC-Pad5)") (class "Default")
      (node (ref "U3") (pin "5") (pinfunction "NC_5") (pintype "passive"))
    )
    (net (code "124") (name "unconnected-(U3-NC-Pad12)") (class "Default")
      (node (ref "U3") (pin "12") (pinfunction "NC_12") (pintype "passive"))
    )
    (net (code "125") (name "unconnected-(U3-NC-Pad13)") (class "Default")
      (node (ref "U3") (pin "13") (pinfunction "NC_13") (pintype "passive"))
    )
  )
)
